# 2x18650Holder.net
KiCad netlist of a schematic drawn in EAGLE
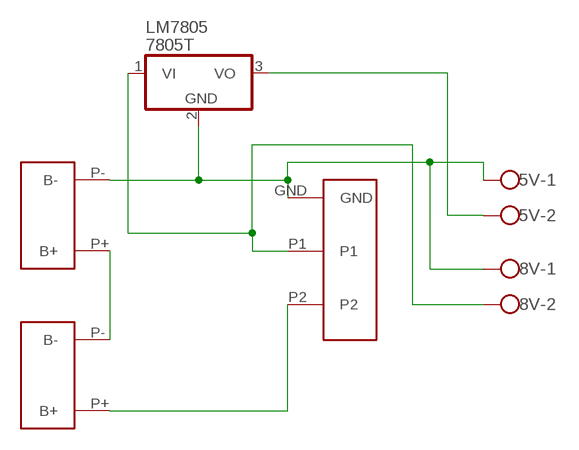
[diagram p0: schematic, sheet 1]

(export (version "E")
  (design (tool "Eeschema 10.0.6"))
  (components
    (comp (ref "5V")
      (value "SCREWCONNECTOR")
      (footprint "eagle-import:2PIN-SCREW-TERMINAL")
      (fields (field (name "MPN") "237-102"))
      (libsource (lib "eagle-import") (part "SCREWCONNECTOR"))
    )
    (comp (ref "8V")
      (value "SCREWCONNECTOR")
      (footprint "eagle-import:2PIN-SCREW-TERMINAL")
      (fields (field (name "MPN") "237-102"))
      (libsource (lib "eagle-import") (part "SCREWCONNECTOR"))
    )
    (comp (ref "LM7805")
      (value "7805T")
      (footprint "eagle-import:TO220H")
      (libsource (lib "eagle-import") (part "78T05"))
    )
    (comp (ref "U$1")
      (value "BATTERY")
      (footprint "eagle-import:BATTERY")
      (libsource (lib "eagle-import") (part "BATTERY"))
    )
    (comp (ref "U$2")
      (value "BATTERY")
      (footprint "eagle-import:BATTERY")
      (libsource (lib "eagle-import") (part "BATTERY"))
    )
    (comp (ref "U$3")
      (value "ROCKER")
      (footprint "eagle-import:ROCKER")
      (libsource (lib "eagle-import") (part "ROCKER"))
    )
  )
  (nets
    (net (code "1") (name "Net-(5VA-KL)") (class "Default")
      (node (ref "5V") (pin "1") (pinfunction "KL_1") (pintype "passive"))
      (node (ref "8V") (pin "1") (pinfunction "KL_1") (pintype "passive"))
      (node (ref "LM7805") (pin "2") (pinfunction "GND_2") (pintype "passive"))
      (node (ref "U$2") (pin "P-") (pinfunction "B-_P-") (pintype "bidirectional"))
      (node (ref "U$3") (pin "GND") (pinfunction "GND_GND") (pintype "bidirectional"))
    )
    (net (code "2") (name "Net-(5VB-KL)") (class "Default")
      (node (ref "5V") (pin "2") (pinfunction "KL_2") (pintype "passive"))
      (node (ref "LM7805") (pin "3") (pinfunction "VO_3") (pintype "passive"))
    )
    (net (code "3") (name "Net-(8VB-KL)") (class "Default")
      (node (ref "8V") (pin "2") (pinfunction "KL_2") (pintype "passive"))
      (node (ref "LM7805") (pin "1") (pinfunction "VI_1") (pintype "input"))
      (node (ref "U$3") (pin "P1") (pinfunction "P1_P1") (pintype "bidirectional"))
    )
    (net (code "4") (name "Net-(U$1-B+)") (class "Default")
      (node (ref "U$1") (pin "P+") (pinfunction "B+_P+") (pintype "bidirectional"))
      (node (ref "U$3") (pin "P2") (pinfunction "P2_P2") (pintype "bidirectional"))
    )
    (net (code "5") (name "Net-(U$1-B-)") (class "Default")
      (node (ref "U$1") (pin "P-") (pinfunction "B-_P-") (pintype "bidirectional"))
      (node (ref "U$2") (pin "P+") (pinfunction "B+_P+") (pintype "bidirectional"))
    )
  )
)
